# SCHEMATIC_MAIN.net
KiCad netlist of a schematic drawn in Altium Designer
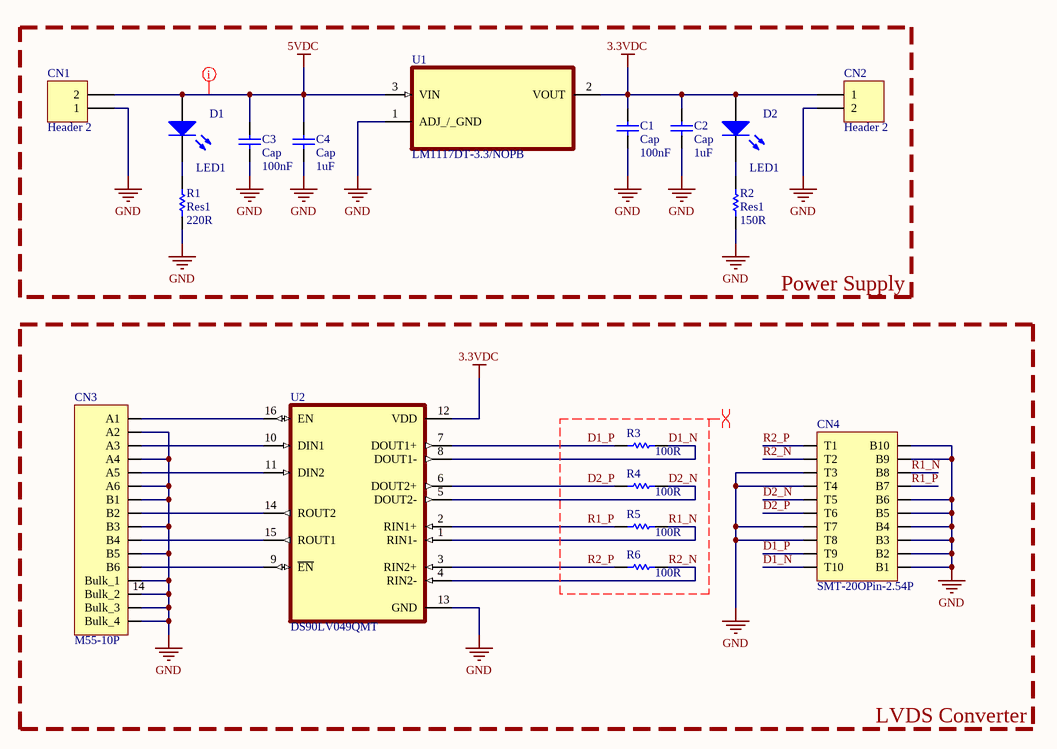
[diagram p0: SCHEMATIC_MAIN.SchDoc]

(export (version "E")
  (design (tool "Eeschema 10.0.6"))
  (components
    (comp (ref "C1")
      (value "Cap")
      (footprint "6-0805_M")
      (description "Capacitor")
      (fields (field (name "ALTIUM_VALUE") "100nF") (field (name "PUBLISHER") "Altium Limited"))
      (libsource (lib "Miscellaneous Devices") (part "Cap"))
    )
    (comp (ref "C2")
      (value "Cap")
      (footprint "6-0805_M")
      (description "Capacitor")
      (fields (field (name "ALTIUM_VALUE") "1uF") (field (name "PUBLISHER") "Altium Limited"))
      (libsource (lib "Miscellaneous Devices") (part "Cap"))
    )
    (comp (ref "C3")
      (value "Cap")
      (footprint "6-0805_M")
      (description "Capacitor")
      (fields (field (name "ALTIUM_VALUE") "100nF") (field (name "PUBLISHER") "Altium Limited"))
      (libsource (lib "Miscellaneous Devices") (part "Cap"))
    )
    (comp (ref "C4")
      (value "Cap")
      (footprint "6-0805_M")
      (description "Capacitor")
      (fields (field (name "ALTIUM_VALUE") "1uF") (field (name "PUBLISHER") "Altium Limited"))
      (libsource (lib "Miscellaneous Devices") (part "Cap"))
    )
    (comp (ref "CN1")
      (value "Header 2")
      (footprint "HDR1X2")
      (description "Header, 2-Pin")
      (fields (field (name "PUBLISHER") "Altium Limited"))
      (libsource (lib "") (part "Header 2_1"))
    )
    (comp (ref "CN2")
      (value "Header 2")
      (footprint "HDR1X2")
      (description "Header, 2-Pin")
      (fields (field (name "PUBLISHER") "Altium Limited"))
      (libsource (lib "Miscellaneous Connectors") (part "Header 2"))
    )
    (comp (ref "CN3")
      (value "M55-10P")
      (footprint "2TH-14SMT")
      (description "10 Position SMD Connector")
      (libsource (lib "M55-7101286646") (part "M55-7101286646"))
    )
    (comp (ref "CN4")
      (value "SMT-20OPin-2.54P")
      (footprint "SMT-20OPin-2.54P")
      (libsource (lib "PCB Based SMT CNs") (part "SMT-20OPin-2.54P"))
    )
    (comp (ref "D1")
      (value "LED1")
      (footprint "6-0805_M")
      (description "Typical RED GaAs LED")
      (fields (field (name "PUBLISHER") "Altium Limited"))
      (libsource (lib "Miscellaneous Devices") (part "LED1"))
    )
    (comp (ref "D2")
      (value "LED1")
      (footprint "6-0805_M")
      (description "Typical RED GaAs LED")
      (fields (field (name "PUBLISHER") "Altium Limited"))
      (libsource (lib "Miscellaneous Devices") (part "LED1"))
    )
    (comp (ref "R1")
      (value "Res1")
      (footprint "6-0805_M")
      (description "Resistor")
      (fields (field (name "ALTIUM_VALUE") "220R") (field (name "PUBLISHER") "Altium Limited"))
      (libsource (lib "Miscellaneous Devices") (part "Res1"))
    )
    (comp (ref "R2")
      (value "Res1")
      (footprint "6-0805_M")
      (description "Resistor")
      (fields (field (name "ALTIUM_VALUE") "150R") (field (name "PUBLISHER") "Altium Limited"))
      (libsource (lib "Miscellaneous Devices") (part "Res1"))
    )
    (comp (ref "R3")
      (value "100R")
      (footprint "6-0805_M")
      (description "Resistor")
      (fields (field (name "Comment") "Res1") (field (name "PUBLISHER") "Altium Limited"))
      (libsource (lib "Miscellaneous Devices") (part "Res1"))
    )
    (comp (ref "R4")
      (value "100R")
      (footprint "6-0805_M")
      (description "Resistor")
      (fields (field (name "Comment") "Res1") (field (name "PUBLISHER") "Altium Limited"))
      (libsource (lib "Miscellaneous Devices") (part "Res1"))
    )
    (comp (ref "R5")
      (value "100R")
      (footprint "6-0805_M")
      (description "Resistor")
      (fields (field (name "Comment") "Res1") (field (name "PUBLISHER") "Altium Limited"))
      (libsource (lib "Miscellaneous Devices") (part "Res1"))
    )
    (comp (ref "R6")
      (value "100R")
      (footprint "6-0805_M")
      (description "Resistor")
      (fields (field (name "Comment") "Res1") (field (name "PUBLISHER") "Altium Limited"))
      (libsource (lib "Miscellaneous Devices") (part "Res1"))
    )
    (comp (ref "U1")
      (value "LM1117DT-3.3/NOPB")
      (footprint "TO228P970X238-3N")
      (description "Linear Voltage Regulator IC 1 Output 800mA TO-252-3")
      (fields (field (name "MP") "LM1117DT33") (field (name "MF") "Texas Instruments"))
      (libsource (lib "LM1117DT-3.3_NOPB") (part "LM1117DT-3.3/NOPB"))
    )
    (comp (ref "U2")
      (value "DS90LV049QMT")
      (footprint "SOP65P640X120-16N")
      (description "Automotive LVDS Dual High-Speed Differential Transceiver 16-TSSOP -40 to 125")
      (fields (field (name "MF") "Texas Instruments") (field (name "MP") "DS90LV049QMT/NOPB"))
      (libsource (lib "DS90LV049QMT") (part "DS90LV049QMT"))
    )
  )
  (nets
    (net (code "1") (name "/D1_N") (class "Default")
      (node (ref "CN4") (pin "10") (pinfunction "T10_10") (pintype "passive"))
      (node (ref "R3") (pin "1") (pinfunction "1_1") (pintype "passive"))
      (node (ref "U2") (pin "8") (pinfunction "DOUT1-_8") (pintype "output"))
    )
    (net (code "2") (name "/D1_P") (class "Default")
      (node (ref "CN4") (pin "9") (pinfunction "T9_9") (pintype "passive"))
      (node (ref "R3") (pin "2") (pinfunction "2_2") (pintype "passive"))
      (node (ref "U2") (pin "7") (pinfunction "DOUT1+_7") (pintype "output"))
    )
    (net (code "3") (name "/D2_N") (class "Default")
      (node (ref "CN4") (pin "5") (pinfunction "T5_5") (pintype "passive"))
      (node (ref "R4") (pin "1") (pinfunction "1_1") (pintype "passive"))
      (node (ref "U2") (pin "5") (pinfunction "DOUT2-_5") (pintype "output"))
    )
    (net (code "4") (name "/D2_P") (class "Default")
      (node (ref "CN4") (pin "6") (pinfunction "T6_6") (pintype "passive"))
      (node (ref "R4") (pin "2") (pinfunction "2_2") (pintype "passive"))
      (node (ref "U2") (pin "6") (pinfunction "DOUT2+_6") (pintype "output"))
    )
    (net (code "5") (name "/R1_N") (class "Default")
      (node (ref "CN4") (pin "18") (pinfunction "B8_18") (pintype "passive"))
      (node (ref "R5") (pin "1") (pinfunction "1_1") (pintype "passive"))
      (node (ref "U2") (pin "1") (pinfunction "RIN1-_1") (pintype "input"))
    )
    (net (code "6") (name "/R1_P") (class "Default")
      (node (ref "CN4") (pin "17") (pinfunction "B7_17") (pintype "passive"))
      (node (ref "R5") (pin "2") (pinfunction "2_2") (pintype "passive"))
      (node (ref "U2") (pin "2") (pinfunction "RIN1+_2") (pintype "input"))
    )
    (net (code "7") (name "/R2_N") (class "Default")
      (node (ref "CN4") (pin "2") (pinfunction "T2_2") (pintype "passive"))
      (node (ref "R6") (pin "1") (pinfunction "1_1") (pintype "passive"))
      (node (ref "U2") (pin "4") (pinfunction "RIN2-_4") (pintype "input"))
    )
    (net (code "8") (name "/R2_P") (class "Default")
      (node (ref "CN4") (pin "1") (pinfunction "T1_1") (pintype "passive"))
      (node (ref "R6") (pin "2") (pinfunction "2_2") (pintype "passive"))
      (node (ref "U2") (pin "3") (pinfunction "RIN2+_3") (pintype "input"))
    )
    (net (code "9") (name "3.3VDC") (class "Default")
      (node (ref "C1") (pin "2") (pinfunction "2_2") (pintype "passive"))
      (node (ref "C2") (pin "2") (pinfunction "2_2") (pintype "passive"))
      (node (ref "CN2") (pin "1") (pinfunction "1_1") (pintype "passive"))
      (node (ref "D2") (pin "1") (pinfunction "A_1") (pintype "passive"))
      (node (ref "U1") (pin "2") (pinfunction "VOUT_2") (pintype "power_in"))
      (node (ref "U2") (pin "12") (pinfunction "VDD_12") (pintype "power_in"))
    )
    (net (code "10") (name "5VDC") (class "Default")
      (node (ref "C3") (pin "2") (pinfunction "2_2") (pintype "passive"))
      (node (ref "C4") (pin "2") (pinfunction "2_2") (pintype "passive"))
      (node (ref "CN1") (pin "2") (pinfunction "2_2") (pintype "passive"))
      (node (ref "D1") (pin "1") (pinfunction "A_1") (pintype "passive"))
      (node (ref "U1") (pin "3") (pinfunction "VIN_3") (pintype "input"))
    )
    (net (code "11") (name "GND") (class "Default")
      (node (ref "C1") (pin "1") (pinfunction "1_1") (pintype "passive"))
      (node (ref "C2") (pin "1") (pinfunction "1_1") (pintype "passive"))
      (node (ref "C3") (pin "1") (pinfunction "1_1") (pintype "passive"))
      (node (ref "C4") (pin "1") (pinfunction "1_1") (pintype "passive"))
      (node (ref "CN1") (pin "1") (pinfunction "1_1") (pintype "passive"))
      (node (ref "CN2") (pin "2") (pinfunction "2_2") (pintype "passive"))
      (node (ref "CN3") (pin "11") (pinfunction "B5_11") (pintype "passive"))
      (node (ref "CN3") (pin "13") (pinfunction "Bulk_1_13") (pintype "passive"))
      (node (ref "CN3") (pin "14") (pinfunction "Bulk_2_14") (pintype "passive"))
      (node (ref "CN3") (pin "15") (pinfunction "Bulk_3_15") (pintype "passive"))
      (node (ref "CN3") (pin "16") (pinfunction "Bulk_4_16") (pintype "passive"))
      (node (ref "CN3") (pin "2") (pinfunction "A2_2") (pintype "passive"))
      (node (ref "CN3") (pin "4") (pinfunction "A4_4") (pintype "passive"))
      (node (ref "CN3") (pin "6") (pinfunction "A6_6") (pintype "passive"))
      (node (ref "CN3") (pin "7") (pinfunction "B1_7") (pintype "passive"))
      (node (ref "CN3") (pin "9") (pinfunction "B3_9") (pintype "passive"))
      (node (ref "CN4") (pin "11") (pinfunction "B1_11") (pintype "passive"))
      (node (ref "CN4") (pin "12") (pinfunction "B2_12") (pintype "passive"))
      (node (ref "CN4") (pin "13") (pinfunction "B3_13") (pintype "passive"))
      (node (ref "CN4") (pin "14") (pinfunction "B4_14") (pintype "passive"))
      (node (ref "CN4") (pin "15") (pinfunction "B5_15") (pintype "passive"))
      (node (ref "CN4") (pin "16") (pinfunction "B6_16") (pintype "passive"))
      (node (ref "CN4") (pin "19") (pinfunction "B9_19") (pintype "passive"))
      (node (ref "CN4") (pin "20") (pinfunction "B10_20") (pintype "passive"))
      (node (ref "CN4") (pin "3") (pinfunction "T3_3") (pintype "passive"))
      (node (ref "CN4") (pin "4") (pinfunction "T4_4") (pintype "passive"))
      (node (ref "CN4") (pin "7") (pinfunction "T7_7") (pintype "passive"))
      (node (ref "CN4") (pin "8") (pinfunction "T8_8") (pintype "passive"))
      (node (ref "R1") (pin "1") (pinfunction "1_1") (pintype "passive"))
      (node (ref "R2") (pin "1") (pinfunction "1_1") (pintype "passive"))
      (node (ref "U1") (pin "1") (pinfunction "ADJ_/_GND_1") (pintype "power_in"))
      (node (ref "U2") (pin "13") (pinfunction "GND_13") (pintype "power_in"))
    )
    (net (code "12") (name "Net-(CN3-A1)") (class "Default")
      (node (ref "CN3") (pin "1") (pinfunction "A1_1") (pintype "passive"))
      (node (ref "U2") (pin "16") (pinfunction "EN_16") (pintype "bidirectional"))
    )
    (net (code "13") (name "Net-(CN3-A3)") (class "Default")
      (node (ref "CN3") (pin "5") (pinfunction "A3_5") (pintype "passive"))
      (node (ref "U2") (pin "10") (pinfunction "DIN1_10") (pintype "input"))
    )
    (net (code "14") (name "Net-(CN3-A5)") (class "Default")
      (node (ref "CN3") (pin "10") (pinfunction "A5_10") (pintype "passive"))
      (node (ref "U2") (pin "11") (pinfunction "DIN2_11") (pintype "input"))
    )
    (net (code "15") (name "Net-(CN3-B2)") (class "Default")
      (node (ref "CN3") (pin "3") (pinfunction "B2_3") (pintype "passive"))
      (node (ref "U2") (pin "14") (pinfunction "ROUT2_14") (pintype "output"))
    )
    (net (code "16") (name "Net-(CN3-B4)") (class "Default")
      (node (ref "CN3") (pin "8") (pinfunction "B4_8") (pintype "passive"))
      (node (ref "U2") (pin "15") (pinfunction "ROUT1_15") (pintype "output"))
    )
    (net (code "17") (name "Net-(CN3-B6)") (class "Default")
      (node (ref "CN3") (pin "12") (pinfunction "B6_12") (pintype "passive"))
      (node (ref "U2") (pin "9") (pinfunction "~{EN}_9") (pintype "bidirectional"))
    )
    (net (code "18") (name "Net-(D1-K)") (class "Default")
      (node (ref "D1") (pin "2") (pinfunction "K_2") (pintype "passive"))
      (node (ref "R1") (pin "2") (pinfunction "2_2") (pintype "passive"))
    )
    (net (code "19") (name "Net-(D2-K)") (class "Default")
      (node (ref "D2") (pin "2") (pinfunction "K_2") (pintype "passive"))
      (node (ref "R2") (pin "2") (pinfunction "2_2") (pintype "passive"))
    )
  )
)
